# PSU.net
KiCad netlist of a schematic drawn in Altium Designer
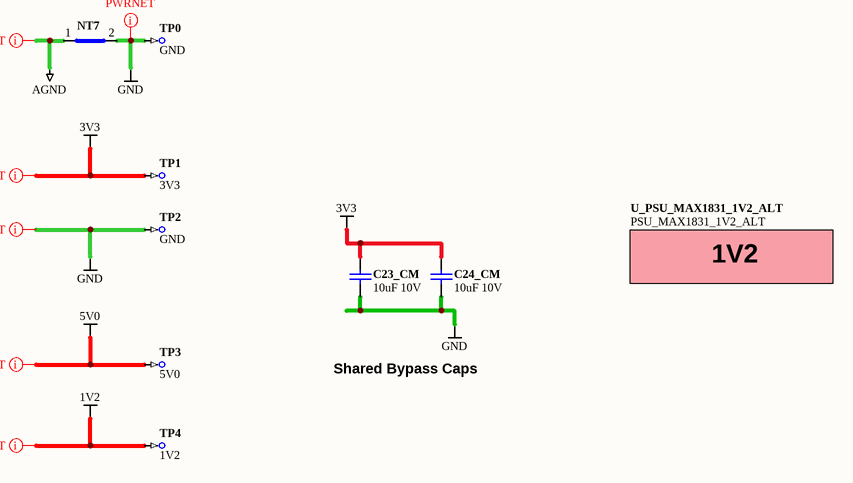
[diagram p0: PSU.SCHDOC]

(export (version "E")
  (design (tool "Eeschema 10.0.6"))
  (components
    (comp (ref "C23_CM")
      (value "10uF 10V")
      (footprint "CAPC2012-STAR")
      (description "Capacitor, Ceramic, 10uF 10% 10V 0805 (2012) X5R")
      (fields (field (name "TOLERANCE") "10 %"))
      (libsource (lib "AltiumDesignLibrary") (part "CAP-NP"))
    )
    (comp (ref "C24_CM")
      (value "10uF 10V")
      (footprint "CAPC2012-STAR")
      (description "Capacitor, Ceramic, 10uF 10% 10V 0805 (2012) X5R")
      (fields (field (name "TOLERANCE") "10 %"))
      (libsource (lib "AltiumDesignLibrary") (part "CAP-NP"))
    )
    (comp (ref "NT7")
      (value "Net Tie SMT2")
      (footprint "NETTIE-SMT2-8X8")
      (description "Net-Tie, Surface Mount, 2 x 0.4mm x 0.2mm SMT Pads - For 0.2mm Track")
      (libsource (lib "AltiumDesignLibrary") (part "NETTIE-SMT2"))
    )
    (comp (ref "TP0")
      (value "GND")
      (footprint "TestPin")
      (description "Test Point, PCB Mount with Silkscreen Box")
      (libsource (lib "AltiumDesignLibrary") (part "TestPin"))
    )
    (comp (ref "TP1")
      (value "3V3")
      (footprint "TestPin")
      (description "Test Point, PCB Mount with Silkscreen Box")
      (libsource (lib "AltiumDesignLibrary") (part "TestPin"))
    )
    (comp (ref "TP2")
      (value "GND")
      (footprint "TestPin")
      (description "Test Point, PCB Mount with Silkscreen Box")
      (libsource (lib "AltiumDesignLibrary") (part "TestPin"))
    )
    (comp (ref "TP3")
      (value "5V0")
      (footprint "TestPin")
      (description "Test Point, PCB Mount with Silkscreen Box")
      (libsource (lib "AltiumDesignLibrary") (part "TestPin"))
    )
    (comp (ref "TP4")
      (value "1V2")
      (footprint "TestPin")
      (description "Test Point, PCB Mount with Silkscreen Box")
      (libsource (lib "AltiumDesignLibrary") (part "TestPin"))
    )
  )
  (nets
    (net (code "1") (name "1V2") (class "Default")
      (node (ref "TP4") (pin "1") (pinfunction "1_1") (pintype "input"))
    )
    (net (code "2") (name "3V3") (class "Default")
      (node (ref "C23_CM") (pin "1") (pinfunction "1_1") (pintype "passive"))
      (node (ref "C24_CM") (pin "1") (pinfunction "1_1") (pintype "passive"))
      (node (ref "TP1") (pin "1") (pinfunction "1_1") (pintype "input"))
    )
    (net (code "3") (name "5V0") (class "Default")
      (node (ref "TP3") (pin "1") (pinfunction "1_1") (pintype "input"))
    )
    (net (code "4") (name "AGND") (class "Default")
      (node (ref "NT7") (pin "1") (pinfunction "Net1_1") (pintype "passive"))
    )
    (net (code "5") (name "GND") (class "Default")
      (node (ref "C23_CM") (pin "2") (pinfunction "2_2") (pintype "passive"))
      (node (ref "C24_CM") (pin "2") (pinfunction "2_2") (pintype "passive"))
      (node (ref "NT7") (pin "2") (pinfunction "Net2_2") (pintype "passive"))
      (node (ref "TP0") (pin "1") (pinfunction "1_1") (pintype "input"))
      (node (ref "TP2") (pin "1") (pinfunction "1_1") (pintype "input"))
    )
  )
)
